# 1Sens.net
KiCad netlist of a schematic drawn in EAGLE
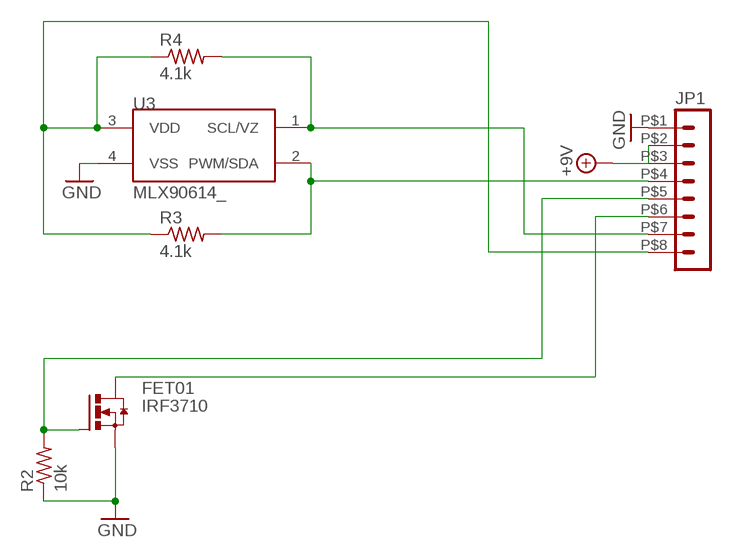
[diagram p0: schematic, sheet 1]

(export (version "E")
  (design (tool "Eeschema 10.0.6"))
  (components
    (comp (ref "FET01")
      (value "IRF3710")
      (footprint "eagle-import:TO220AH")
      (libsource (lib "eagle-import") (part "IRF3704"))
    )
    (comp (ref "JP1")
      (value "HEADER_POS8_43045-0800")
      (footprint "eagle-import:43045-0800")
      (libsource (lib "eagle-import") (part "HEADER_POS8_?43045-0800"))
    )
    (comp (ref "R2")
      (value "10k")
      (footprint "eagle-import:0207_7")
      (libsource (lib "eagle-import") (part "R-US_0207/7"))
    )
    (comp (ref "R3")
      (value "4.1k")
      (footprint "eagle-import:0204_5")
      (libsource (lib "eagle-import") (part "R-US_0204/5"))
    )
    (comp (ref "R4")
      (value "4.1k")
      (footprint "eagle-import:0204_5")
      (libsource (lib "eagle-import") (part "R-US_0204/5"))
    )
    (comp (ref "U3")
      (value "MLX90614_")
      (footprint "eagle-import:TO-39")
      (libsource (lib "eagle-import") (part "MLX90614_"))
    )
  )
  (nets
    (net (code "1") (name "+9V") (class "Default")
      (node (ref "JP1") (pin "P$2") (pinfunction "2_P$2") (pintype "passive"))
      (node (ref "JP1") (pin "P$3") (pinfunction "3_P$3") (pintype "passive"))
    )
    (net (code "2") (name "GND") (class "Default")
      (node (ref "FET01") (pin "E") (pinfunction "S_E") (pintype "passive"))
      (node (ref "JP1") (pin "P$1") (pinfunction "1_P$1") (pintype "passive"))
      (node (ref "R2") (pin "1") (pinfunction "1_1") (pintype "passive"))
      (node (ref "U3") (pin "4") (pinfunction "VSS_4") (pintype "bidirectional"))
    )
    (net (code "3") (name "Net-(FET01-D)") (class "Default")
      (node (ref "FET01") (pin "C") (pinfunction "D_C") (pintype "passive"))
      (node (ref "JP1") (pin "P$6") (pinfunction "6_P$6") (pintype "passive"))
    )
    (net (code "4") (name "Net-(FET01-G)") (class "Default")
      (node (ref "FET01") (pin "B") (pinfunction "G_B") (pintype "passive"))
      (node (ref "JP1") (pin "P$5") (pinfunction "5_P$5") (pintype "passive"))
      (node (ref "R2") (pin "2") (pinfunction "2_2") (pintype "passive"))
    )
    (net (code "5") (name "Net-(JP1-4)") (class "Default")
      (node (ref "JP1") (pin "P$4") (pinfunction "4_P$4") (pintype "passive"))
      (node (ref "R3") (pin "2") (pinfunction "2_2") (pintype "passive"))
      (node (ref "U3") (pin "2") (pinfunction "PWM/SDA_2") (pintype "bidirectional"))
    )
    (net (code "6") (name "Net-(JP1-7)") (class "Default")
      (node (ref "JP1") (pin "P$7") (pinfunction "7_P$7") (pintype "passive"))
      (node (ref "R4") (pin "2") (pinfunction "2_2") (pintype "passive"))
      (node (ref "U3") (pin "1") (pinfunction "SCL/VZ_1") (pintype "bidirectional"))
    )
    (net (code "7") (name "Net-(JP1-8)") (class "Default")
      (node (ref "JP1") (pin "P$8") (pinfunction "8_P$8") (pintype "passive"))
      (node (ref "R3") (pin "1") (pinfunction "1_1") (pintype "passive"))
      (node (ref "R4") (pin "1") (pinfunction "1_1") (pintype "passive"))
      (node (ref "U3") (pin "3") (pinfunction "VDD_3") (pintype "bidirectional"))
    )
  )
)
